# SCH_robot_2026-01-04.net
KiCad netlist of a schematic drawn in EasyEDA
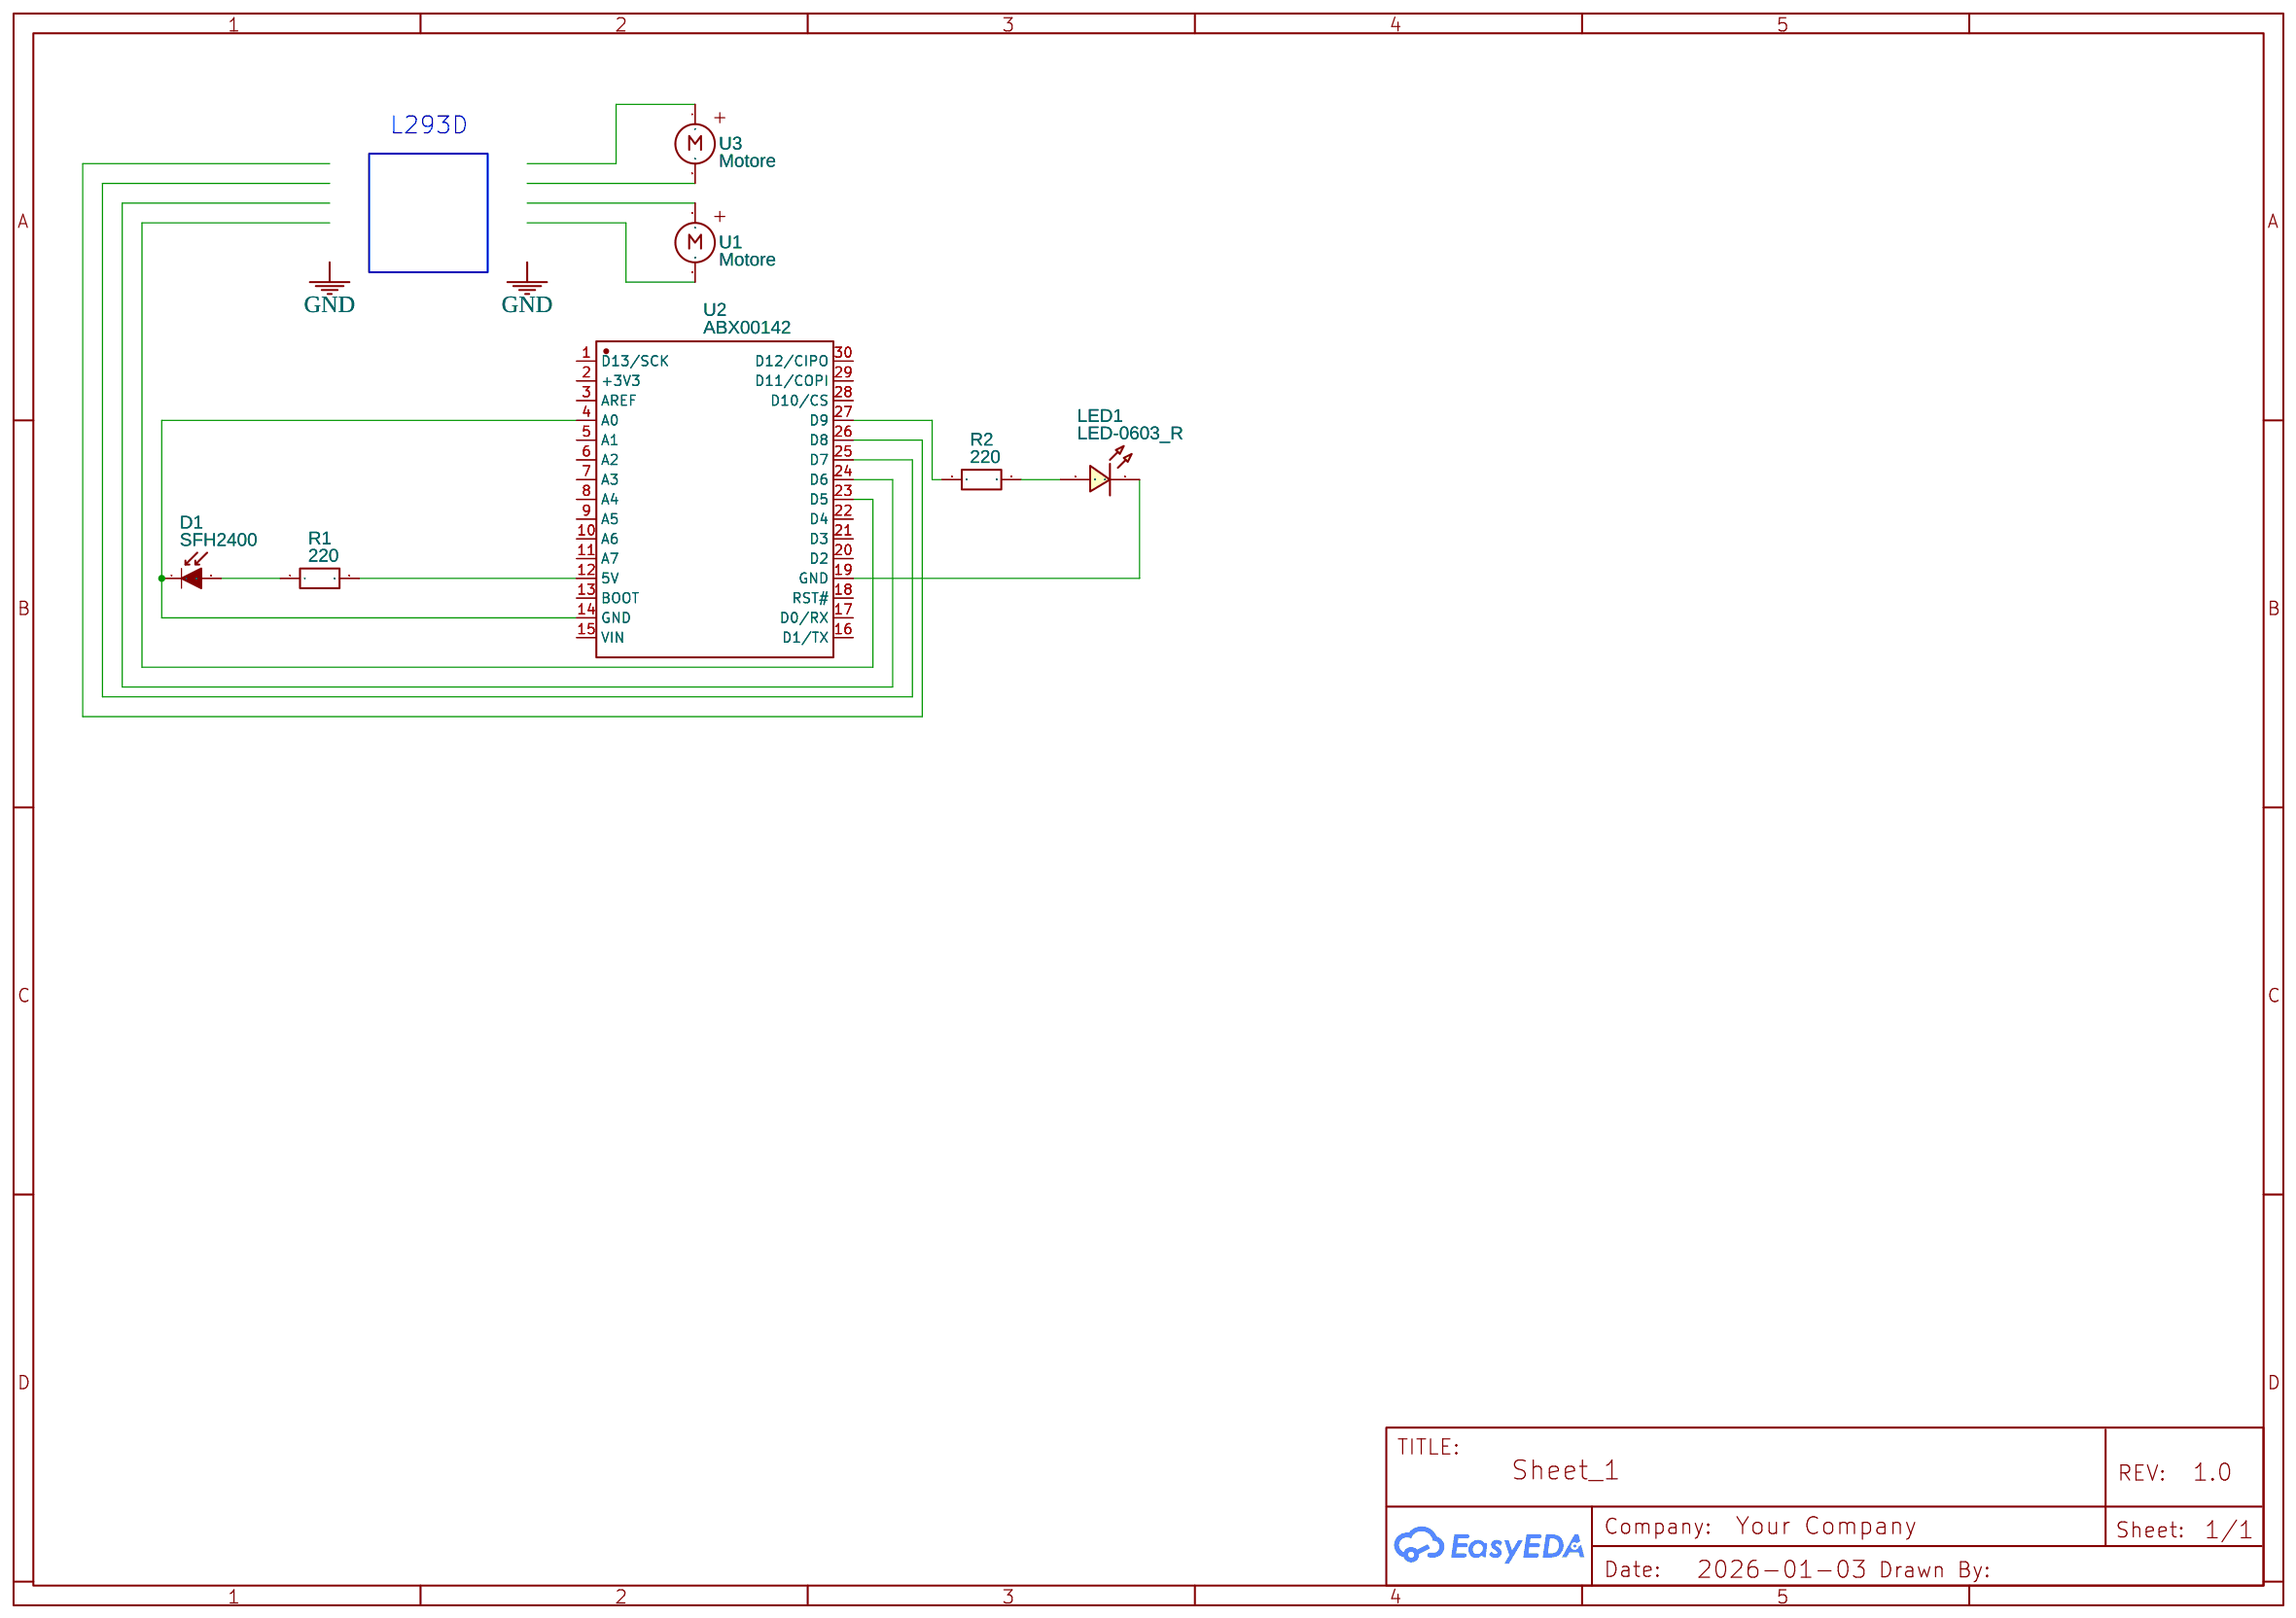
[diagram p0: schematic sheet]

(export (version "E")
  (design (tool "Eeschema 10.0.6"))
  (components
    (comp (ref "D1") (value "SFH2400") (libsource (lib "") (part "SFH2400")))
    (comp (ref "LED1")
      (value "LED-0603_R")
      (fields
        (field (name "Manufacturer Part") "19-217/R6C-AL1M2VY/3T")
        (field (name "Manufacturer") "EVERLIGHT(台湾亿光)")
      )
      (libsource (lib "") (part "LED-0603_R"))
    )
    (comp (ref "R1") (value "220") (libsource (lib "") (part "R_0603_EU")))
    (comp (ref "R2") (value "220") (libsource (lib "") (part "R_0603_EU")))
    (comp (ref "U1") (value "Motore") (libsource (lib "") (part "Motore")))
    (comp (ref "U2") (value "ABX00142") (libsource (lib "") (part "ABX00142")))
    (comp (ref "U3") (value "Motore") (libsource (lib "") (part "Motore")))
  )
  (nets
    (net (code "2") (name "Net-(D1-A)") (class "Default")
      (node (ref "D1") (pin "2") (pinfunction "A_2") (pintype "unspecified"))
      (node (ref "R1") (pin "1") (pinfunction "1_1") (pintype "unspecified"))
    )
    (net (code "3") (name "Net-(D1-K)") (class "Default")
      (node (ref "D1") (pin "1") (pinfunction "K_1") (pintype "unspecified"))
      (node (ref "U2") (pin "14") (pinfunction "GND_14") (pintype "unspecified"))
      (node (ref "U2") (pin "4") (pinfunction "A0_4") (pintype "unspecified"))
    )
    (net (code "4") (name "Net-(LED1-Pad1)") (class "Default")
      (node (ref "LED1") (pin "1") (pinfunction "1_1") (pintype "unspecified"))
      (node (ref "R2") (pin "2") (pinfunction "2_2") (pintype "unspecified"))
    )
    (net (code "5") (name "Net-(LED1-Pad2)") (class "Default")
      (node (ref "LED1") (pin "2") (pinfunction "2_2") (pintype "unspecified"))
      (node (ref "U2") (pin "19") (pinfunction "GND_19") (pintype "unspecified"))
    )
    (net (code "6") (name "Net-(U2-5V)") (class "Default")
      (node (ref "R1") (pin "2") (pinfunction "2_2") (pintype "unspecified"))
      (node (ref "U2") (pin "12") (pinfunction "5V_12") (pintype "unspecified"))
    )
    (net (code "7") (name "Net-(U2-D9)") (class "Default")
      (node (ref "R2") (pin "1") (pinfunction "1_1") (pintype "unspecified"))
      (node (ref "U2") (pin "27") (pinfunction "D9_27") (pintype "unspecified"))
    )
    (net (code "8") (name "unconnected-(U1-Pad1)") (class "Default")
      (node (ref "U1") (pin "1") (pinfunction "1_1") (pintype "unspecified"))
    )
    (net (code "9") (name "unconnected-(U1-Pad2)") (class "Default")
      (node (ref "U1") (pin "2") (pinfunction "2_2") (pintype "unspecified"))
    )
    (net (code "10") (name "unconnected-(U2-+3V3-Pad2)") (class "Default")
      (node (ref "U2") (pin "2") (pinfunction "+3V3_2") (pintype "unspecified"))
    )
    (net (code "11") (name "unconnected-(U2-A1-Pad5)") (class "Default")
      (node (ref "U2") (pin "5") (pinfunction "A1_5") (pintype "unspecified"))
    )
    (net (code "12") (name "unconnected-(U2-A2-Pad6)") (class "Default")
      (node (ref "U2") (pin "6") (pinfunction "A2_6") (pintype "unspecified"))
    )
    (net (code "13") (name "unconnected-(U2-A3-Pad7)") (class "Default")
      (node (ref "U2") (pin "7") (pinfunction "A3_7") (pintype "unspecified"))
    )
    (net (code "14") (name "unconnected-(U2-A4-Pad8)") (class "Default")
      (node (ref "U2") (pin "8") (pinfunction "A4_8") (pintype "unspecified"))
    )
    (net (code "15") (name "unconnected-(U2-A5-Pad9)") (class "Default")
      (node (ref "U2") (pin "9") (pinfunction "A5_9") (pintype "unspecified"))
    )
    (net (code "16") (name "unconnected-(U2-A6-Pad10)") (class "Default")
      (node (ref "U2") (pin "10") (pinfunction "A6_10") (pintype "unspecified"))
    )
    (net (code "17") (name "unconnected-(U2-A7-Pad11)") (class "Default")
      (node (ref "U2") (pin "11") (pinfunction "A7_11") (pintype "unspecified"))
    )
    (net (code "18") (name "unconnected-(U2-AREF-Pad3)") (class "Default")
      (node (ref "U2") (pin "3") (pinfunction "AREF_3") (pintype "unspecified"))
    )
    (net (code "19") (name "unconnected-(U2-BOOT-Pad13)") (class "Default")
      (node (ref "U2") (pin "13") (pinfunction "BOOT_13") (pintype "unspecified"))
    )
    (net (code "20") (name "unconnected-(U2-D0{slash}RX-Pad17)") (class "Default")
      (node (ref "U2") (pin "17") (pinfunction "D0/RX_17") (pintype "unspecified"))
    )
    (net (code "21") (name "unconnected-(U2-D1{slash}TX-Pad16)") (class "Default")
      (node (ref "U2") (pin "16") (pinfunction "D1/TX_16") (pintype "unspecified"))
    )
    (net (code "22") (name "unconnected-(U2-D2-Pad20)") (class "Default")
      (node (ref "U2") (pin "20") (pinfunction "D2_20") (pintype "unspecified"))
    )
    (net (code "23") (name "unconnected-(U2-D3-Pad21)") (class "Default")
      (node (ref "U2") (pin "21") (pinfunction "D3_21") (pintype "unspecified"))
    )
    (net (code "24") (name "unconnected-(U2-D4-Pad22)") (class "Default")
      (node (ref "U2") (pin "22") (pinfunction "D4_22") (pintype "unspecified"))
    )
    (net (code "25") (name "unconnected-(U2-D5-Pad23)") (class "Default")
      (node (ref "U2") (pin "23") (pinfunction "D5_23") (pintype "unspecified"))
    )
    (net (code "26") (name "unconnected-(U2-D6-Pad24)") (class "Default")
      (node (ref "U2") (pin "24") (pinfunction "D6_24") (pintype "unspecified"))
    )
    (net (code "27") (name "unconnected-(U2-D7-Pad25)") (class "Default")
      (node (ref "U2") (pin "25") (pinfunction "D7_25") (pintype "unspecified"))
    )
    (net (code "28") (name "unconnected-(U2-D8-Pad26)") (class "Default")
      (node (ref "U2") (pin "26") (pinfunction "D8_26") (pintype "unspecified"))
    )
    (net (code "29") (name "unconnected-(U2-D10{slash}CS-Pad28)") (class "Default")
      (node (ref "U2") (pin "28") (pinfunction "D10/CS_28") (pintype "unspecified"))
    )
    (net (code "30") (name "unconnected-(U2-D11{slash}COPI-Pad29)") (class "Default")
      (node (ref "U2") (pin "29") (pinfunction "D11/COPI_29") (pintype "unspecified"))
    )
    (net (code "31") (name "unconnected-(U2-D12{slash}CIPO-Pad30)") (class "Default")
      (node (ref "U2") (pin "30") (pinfunction "D12/CIPO_30") (pintype "unspecified"))
    )
    (net (code "32") (name "unconnected-(U2-D13{slash}SCK-Pad1)") (class "Default")
      (node (ref "U2") (pin "1") (pinfunction "D13/SCK_1") (pintype "unspecified"))
    )
    (net (code "33") (name "unconnected-(U2-RST#-Pad18)") (class "Default")
      (node (ref "U2") (pin "18") (pinfunction "RST#_18") (pintype "unspecified"))
    )
    (net (code "34") (name "unconnected-(U2-VIN-Pad15)") (class "Default")
      (node (ref "U2") (pin "15") (pinfunction "VIN_15") (pintype "unspecified"))
    )
    (net (code "35") (name "unconnected-(U3-Pad1)") (class "Default")
      (node (ref "U3") (pin "1") (pinfunction "1_1") (pintype "unspecified"))
    )
    (net (code "36") (name "unconnected-(U3-Pad2)") (class "Default")
      (node (ref "U3") (pin "2") (pinfunction "2_2") (pintype "unspecified"))
    )
  )
)
